# esame1207schematico.net
KiCad netlist of a schematic drawn in Altium Designer
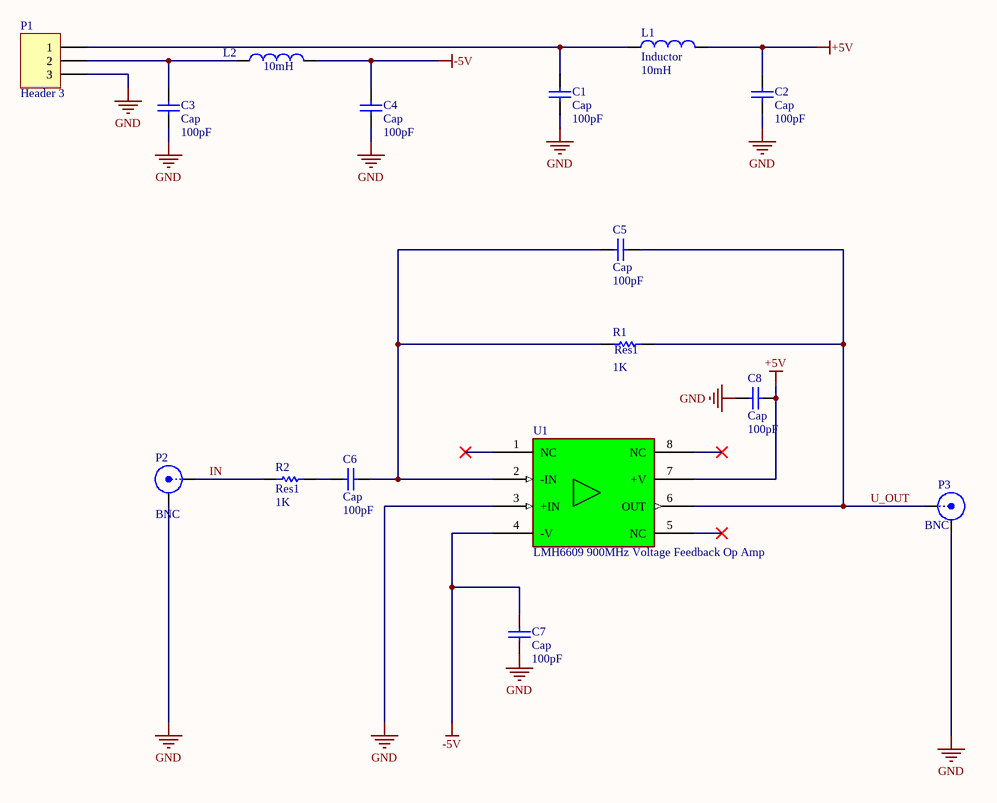
[diagram p0: esame1207schematico.SchDoc]

(export (version "E")
  (design (tool "Eeschema 10.0.6"))
  (components
    (comp (ref "C1")
      (value "Cap")
      (footprint "0603 Comp")
      (description "Capacitor")
      (fields (field (name "ALTIUM_VALUE") "100pF") (field (name "PUBLISHER") "Altium Limited"))
      (libsource (lib "Miscellaneous Devices") (part "Cap"))
    )
    (comp (ref "C2")
      (value "Cap")
      (footprint "0603 Comp")
      (description "Capacitor")
      (fields (field (name "ALTIUM_VALUE") "100pF") (field (name "PUBLISHER") "Altium Limited"))
      (libsource (lib "Miscellaneous Devices") (part "Cap"))
    )
    (comp (ref "C3")
      (value "Cap")
      (footprint "0603 Comp")
      (description "Capacitor")
      (fields (field (name "ALTIUM_VALUE") "100pF") (field (name "PUBLISHER") "Altium Limited"))
      (libsource (lib "Miscellaneous Devices") (part "Cap"))
    )
    (comp (ref "C4")
      (value "Cap")
      (footprint "0603 Comp")
      (description "Capacitor")
      (fields (field (name "ALTIUM_VALUE") "100pF") (field (name "PUBLISHER") "Altium Limited"))
      (libsource (lib "Miscellaneous Devices") (part "Cap"))
    )
    (comp (ref "C5")
      (value "Cap")
      (footprint "0603 Comp")
      (description "Capacitor")
      (fields (field (name "ALTIUM_VALUE") "100pF") (field (name "PUBLISHER") "Altium Limited"))
      (libsource (lib "Miscellaneous Devices") (part "Cap"))
    )
    (comp (ref "C6")
      (value "Cap")
      (footprint "0603 Comp")
      (description "Capacitor")
      (fields (field (name "ALTIUM_VALUE") "100pF") (field (name "PUBLISHER") "Altium Limited"))
      (libsource (lib "Miscellaneous Devices") (part "Cap"))
    )
    (comp (ref "C7")
      (value "Cap")
      (footprint "0603 Comp")
      (description "Capacitor")
      (fields (field (name "ALTIUM_VALUE") "100pF") (field (name "PUBLISHER") "Altium Limited"))
      (libsource (lib "Miscellaneous Devices") (part "Cap"))
    )
    (comp (ref "C8")
      (value "Cap")
      (footprint "0603 Comp")
      (description "Capacitor")
      (fields (field (name "ALTIUM_VALUE") "100pF") (field (name "PUBLISHER") "Altium Limited"))
      (libsource (lib "Miscellaneous Devices") (part "Cap"))
    )
    (comp (ref "L1")
      (value "Inductor")
      (footprint "0603 Comp")
      (fields (field (name "ALTIUM_VALUE") "10mH") (field (name "PUBLISHER") "Altium Limited"))
      (libsource (lib "Miscellaneous Devices") (part "Inductor"))
    )
    (comp (ref "L2")
      (value "10mH")
      (footprint "0603 Comp")
      (description "Inductor")
      (fields (field (name "PUBLISHER") "Altium Limited"))
      (libsource (lib "Miscellaneous Devices") (part "Inductor"))
    )
    (comp (ref "P1")
      (value "Header 3")
      (footprint "HDR1X3")
      (description "Header, 3-Pin")
      (fields (field (name "PUBLISHER") "Altium Limited"))
      (libsource (lib "Miscellaneous Connectors") (part "Header 3"))
    )
    (comp (ref "P2")
      (value "BNC")
      (footprint "SMB_V-RJ45")
      (description "BNC Elbow Connector")
      (fields (field (name "PUBLISHER") "Altium Limited"))
      (libsource (lib "Miscellaneous Connectors") (part "BNC"))
    )
    (comp (ref "P3")
      (value "BNC")
      (footprint "SMB_V-RJ45")
      (description "BNC Elbow Connector")
      (fields (field (name "PUBLISHER") "Altium Limited"))
      (libsource (lib "Miscellaneous Connectors") (part "BNC"))
    )
    (comp (ref "R1")
      (value "Res1")
      (footprint "0603 Comp")
      (description "Resistor")
      (fields (field (name "ALTIUM_VALUE") "1K") (field (name "PUBLISHER") "Altium Limited"))
      (libsource (lib "Miscellaneous Devices") (part "Res1"))
    )
    (comp (ref "R2")
      (value "Res1")
      (footprint "0603 Comp")
      (description "Resistor")
      (fields (field (name "ALTIUM_VALUE") "1K") (field (name "PUBLISHER") "Altium Limited"))
      (libsource (lib "Miscellaneous Devices") (part "Res1"))
    )
    (comp (ref "U1")
      (value "LMH6609 900MHz Voltage Feedback Op Amp")
      (footprint "SOIC")
      (libsource (lib "Schlib1") (part "LMA6609"))
    )
  )
  (nets
    (net (code "1") (name "+5V") (class "Default")
      (node (ref "C2") (pin "2") (pinfunction "2_2") (pintype "passive"))
      (node (ref "C8") (pin "1") (pinfunction "1_1") (pintype "passive"))
      (node (ref "L1") (pin "2") (pinfunction "2_2") (pintype "passive"))
      (node (ref "U1") (pin "7") (pinfunction "+V_7") (pintype "power_in"))
    )
    (net (code "2") (name "-5V") (class "Default")
      (node (ref "C4") (pin "2") (pinfunction "2_2") (pintype "passive"))
      (node (ref "C7") (pin "2") (pinfunction "2_2") (pintype "passive"))
      (node (ref "L2") (pin "2") (pinfunction "2_2") (pintype "passive"))
      (node (ref "U1") (pin "4") (pinfunction "-V_4") (pintype "power_in"))
    )
    (net (code "3") (name "/IN") (class "Default")
      (node (ref "P2") (pin "1") (pinfunction "X_1") (pintype "passive"))
      (node (ref "R2") (pin "2") (pinfunction "2_2") (pintype "passive"))
    )
    (net (code "4") (name "/U_OUT") (class "Default")
      (node (ref "C5") (pin "2") (pinfunction "2_2") (pintype "passive"))
      (node (ref "P3") (pin "1") (pinfunction "X_1") (pintype "passive"))
      (node (ref "R1") (pin "2") (pinfunction "2_2") (pintype "passive"))
      (node (ref "U1") (pin "6") (pinfunction "OUT_6") (pintype "output"))
    )
    (net (code "5") (name "GND") (class "Default")
      (node (ref "C1") (pin "1") (pinfunction "1_1") (pintype "passive"))
      (node (ref "C2") (pin "1") (pinfunction "1_1") (pintype "passive"))
      (node (ref "C3") (pin "1") (pinfunction "1_1") (pintype "passive"))
      (node (ref "C4") (pin "1") (pinfunction "1_1") (pintype "passive"))
      (node (ref "C7") (pin "1") (pinfunction "1_1") (pintype "passive"))
      (node (ref "C8") (pin "2") (pinfunction "2_2") (pintype "passive"))
      (node (ref "P1") (pin "3") (pinfunction "3_3") (pintype "passive"))
      (node (ref "P2") (pin "2") (pinfunction "Y_2") (pintype "passive"))
      (node (ref "P3") (pin "2") (pinfunction "Y_2") (pintype "passive"))
      (node (ref "U1") (pin "3") (pinfunction "+IN_3") (pintype "input"))
    )
    (net (code "6") (name "Net-(C1-Pad2)") (class "Default")
      (node (ref "C1") (pin "2") (pinfunction "2_2") (pintype "passive"))
      (node (ref "L1") (pin "1") (pinfunction "1_1") (pintype "passive"))
      (node (ref "P1") (pin "1") (pinfunction "1_1") (pintype "passive"))
    )
    (net (code "7") (name "Net-(C3-Pad2)") (class "Default")
      (node (ref "C3") (pin "2") (pinfunction "2_2") (pintype "passive"))
      (node (ref "L2") (pin "1") (pinfunction "1_1") (pintype "passive"))
      (node (ref "P1") (pin "2") (pinfunction "2_2") (pintype "passive"))
    )
    (net (code "8") (name "Net-(C6-Pad1)") (class "Default")
      (node (ref "C6") (pin "1") (pinfunction "1_1") (pintype "passive"))
      (node (ref "R2") (pin "1") (pinfunction "1_1") (pintype "passive"))
    )
    (net (code "9") (name "Net-(U1--IN)") (class "Default")
      (node (ref "C5") (pin "1") (pinfunction "1_1") (pintype "passive"))
      (node (ref "C6") (pin "2") (pinfunction "2_2") (pintype "passive"))
      (node (ref "R1") (pin "1") (pinfunction "1_1") (pintype "passive"))
      (node (ref "U1") (pin "2") (pinfunction "-IN_2") (pintype "input"))
    )
    (net (code "10") (name "unconnected-(U1-NC-Pad1)") (class "Default")
      (node (ref "U1") (pin "1") (pinfunction "NC_1") (pintype "passive+no_connect"))
    )
    (net (code "11") (name "unconnected-(U1-NC-Pad5)") (class "Default")
      (node (ref "U1") (pin "5") (pinfunction "NC_5") (pintype "passive+no_connect"))
    )
    (net (code "12") (name "unconnected-(U1-NC-Pad8)") (class "Default")
      (node (ref "U1") (pin "8") (pinfunction "NC_8") (pintype "passive+no_connect"))
    )
  )
)
